# C_lula_3.net
KiCad netlist of a schematic drawn in Altium Designer
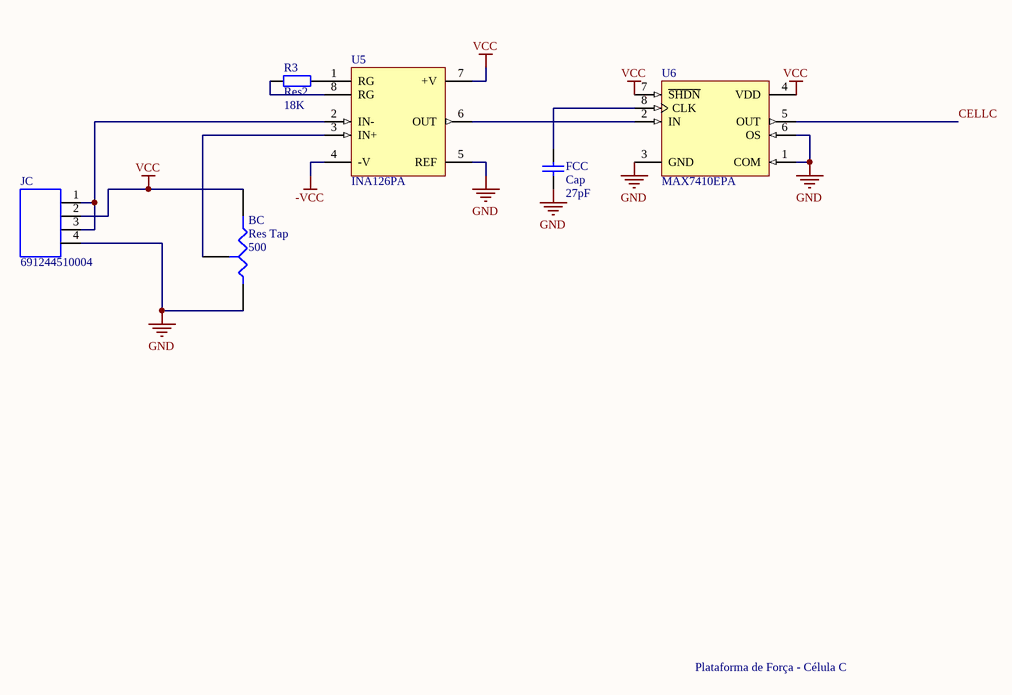
[diagram p0: Célula 3.SchDoc]

(export (version "E")
  (design (tool "Eeschema 10.0.6"))
  (components
    (comp (ref "BC")
      (value "Res Tap")
      (footprint "PcbLib1:TSR3006")
      (description "Tapped Resistor")
      (fields (field (name "ALTIUM_VALUE") "500") (field (name "PUBLISHER") "Altium Limited"))
      (libsource (lib "Miscellaneous Devices") (part "Res Tap"))
    )
    (comp (ref "FCC")
      (value "Cap")
      (footprint "RAD-0.3")
      (description "Capacitor")
      (fields (field (name "ALTIUM_VALUE") "27pF") (field (name "PUBLISHER") "Altium Limited"))
      (libsource (lib "Miscellaneous Devices") (part "Cap"))
    )
    (comp (ref "JC")
      (value "691244510004")
      (footprint "691244510004")
      (description "WR-TBL Horizontal Cable Entry With Rising Cage Clamp,Serie 2445 - 5.08 mm")
      (fields (field (name "MANUFACTURER") "Wurth Elektronik") (field (name "CREATED BY") "Baojun Chen"))
      (libsource (lib "WE_WR-TBL_Rising Cage System_5.08 mm_rev15b") (part "691244510004"))
    )
    (comp (ref "R3")
      (value "Res2")
      (footprint "AXIAL-0.4")
      (description "Resistor")
      (fields (field (name "ALTIUM_VALUE") "18K") (field (name "PUBLISHER") "Altium Limited"))
      (libsource (lib "Miscellaneous Devices") (part "Res2"))
    )
    (comp (ref "U5")
      (value "INA126PA")
      (footprint "006E")
      (description "Precision, Low-Power Instrumentation Amplifiers")
      (fields (field (name "PUBLISHER") "Altium Limited"))
      (libsource (lib "Placa") (part "INA126PA"))
    )
    (comp (ref "U6")
      (value "MAX7410EPA")
      (footprint "PA8")
      (description "5th-Order, Lowpass, Switched-Capacitor Filter")
      (fields (field (name "PUBLISHER") "Altium Limited"))
      (libsource (lib "Maxim Filter Switched Capacitor") (part "MAX7410EPA"))
    )
  )
  (nets
    (net (code "1") (name "-VCC") (class "Default")
      (node (ref "U5") (pin "4") (pinfunction "-V_4") (pintype "power_in"))
    )
    (net (code "2") (name "/CELLC") (class "Default")
      (node (ref "U6") (pin "5") (pinfunction "OUT_5") (pintype "output"))
    )
    (net (code "3") (name "GND") (class "Default")
      (node (ref "BC") (pin "1") (pinfunction "A_1") (pintype "passive"))
      (node (ref "FCC") (pin "1") (pinfunction "1_1") (pintype "passive"))
      (node (ref "JC") (pin "4") (pinfunction "4_4") (pintype "passive"))
      (node (ref "U5") (pin "5") (pinfunction "REF_5") (pintype "passive"))
      (node (ref "U6") (pin "1") (pinfunction "COM_1") (pintype "input"))
      (node (ref "U6") (pin "3") (pinfunction "GND_3") (pintype "power_in"))
      (node (ref "U6") (pin "6") (pinfunction "OS_6") (pintype "input"))
    )
    (net (code "4") (name "Net-(BC-TAP)") (class "Default")
      (node (ref "BC") (pin "3") (pinfunction "TAP_3") (pintype "passive"))
      (node (ref "U5") (pin "3") (pinfunction "IN+_3") (pintype "input"))
    )
    (net (code "5") (name "Net-(R3-Pad1)") (class "Default")
      (node (ref "R3") (pin "1") (pinfunction "1_1") (pintype "passive"))
      (node (ref "U5") (pin "8") (pinfunction "RG_8") (pintype "passive"))
    )
    (net (code "6") (name "Net-(R3-Pad2)") (class "Default")
      (node (ref "R3") (pin "2") (pinfunction "2_2") (pintype "passive"))
      (node (ref "U5") (pin "1") (pinfunction "RG_1") (pintype "passive"))
    )
    (net (code "7") (name "Net-(U5-IN-)") (class "Default")
      (node (ref "JC") (pin "1") (pinfunction "1_1") (pintype "passive"))
      (node (ref "JC") (pin "3") (pinfunction "3_3") (pintype "passive"))
      (node (ref "U5") (pin "2") (pinfunction "IN-_2") (pintype "input"))
    )
    (net (code "8") (name "Net-(U5-OUT)") (class "Default")
      (node (ref "U5") (pin "6") (pinfunction "OUT_6") (pintype "output"))
      (node (ref "U6") (pin "2") (pinfunction "IN_2") (pintype "input"))
    )
    (net (code "9") (name "Net-(U6-CLK)") (class "Default")
      (node (ref "FCC") (pin "2") (pinfunction "2_2") (pintype "passive"))
      (node (ref "U6") (pin "8") (pinfunction "CLK_8") (pintype "input"))
    )
    (net (code "10") (name "VCC") (class "Default")
      (node (ref "BC") (pin "2") (pinfunction "B_2") (pintype "passive"))
      (node (ref "JC") (pin "2") (pinfunction "2_2") (pintype "passive"))
      (node (ref "U5") (pin "7") (pinfunction "+V_7") (pintype "power_in"))
      (node (ref "U6") (pin "4") (pinfunction "VDD_4") (pintype "power_in"))
      (node (ref "U6") (pin "7") (pinfunction "~{SHDN}_7") (pintype "input"))
    )
  )
)
